# blinky_tag_smt_ver_1.net
KiCad netlist of a schematic drawn in EAGLE
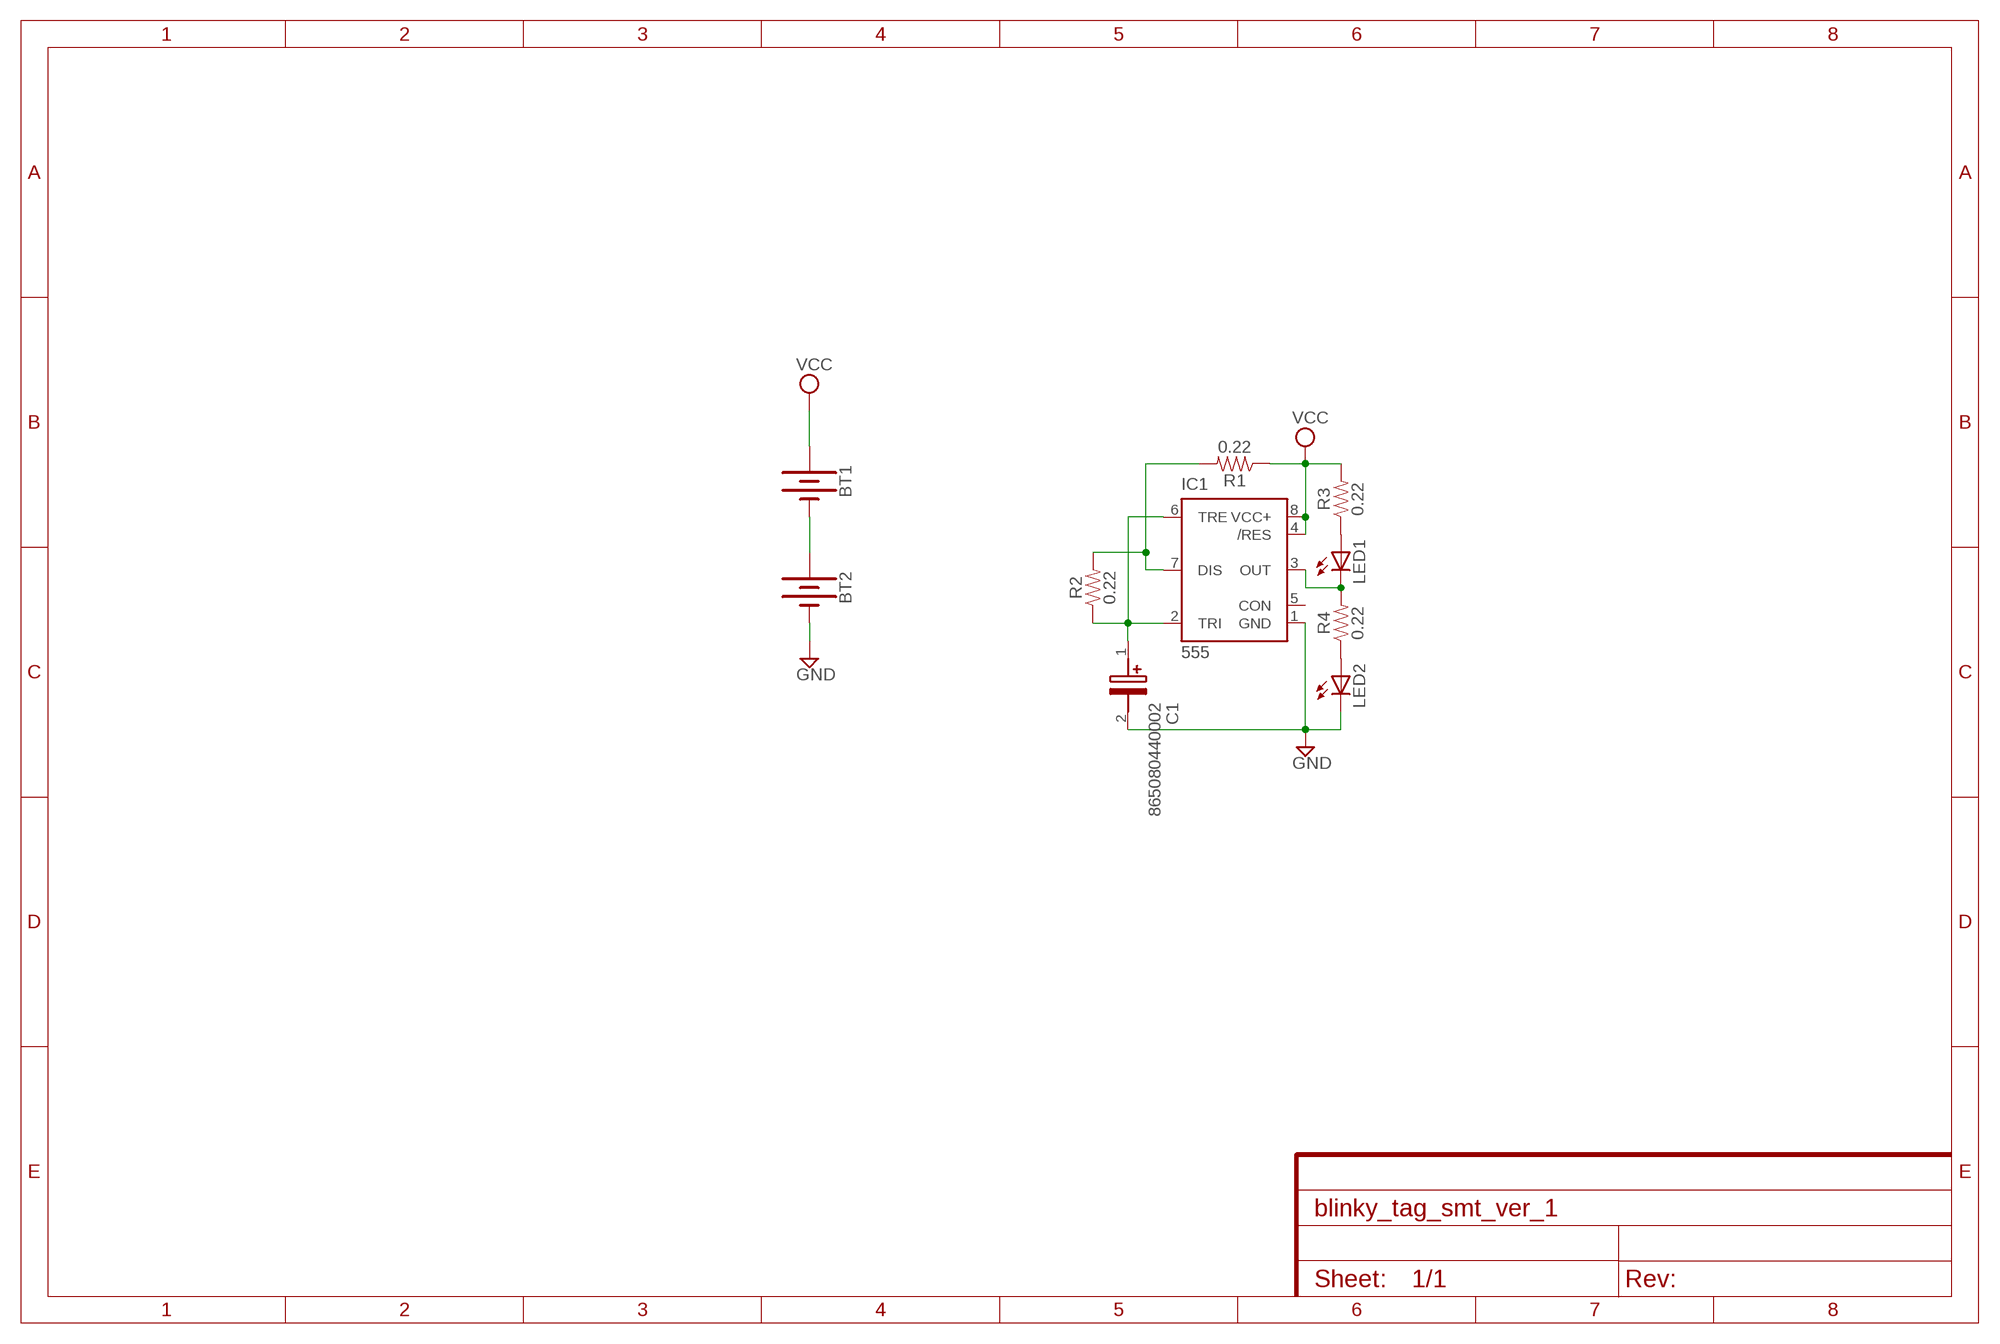
[diagram p0: schematic, sheet 1]

(export (version "E")
  (design (tool "Eeschema 10.0.6"))
  (components
    (comp (ref "BT1")
      (value "BATTERY-12MM_SMD")
      (footprint "eagle-import:BATTCON_12MM")
      (libsource (lib "eagle-import") (part "BATTERY-12MM_SMD"))
    )
    (comp (ref "BT2")
      (value "BATTERY-12MM_SMD")
      (footprint "eagle-import:BATTCON_12MM")
      (libsource (lib "eagle-import") (part "BATTERY-12MM_SMD"))
    )
    (comp (ref "C1")
      (value "865080440002")
      (footprint "eagle-import:CAPAE400X550N")
      (fields
        (field (name "MOUSER_PART_NUMBER") "710-865080440002")
        (field (name "RS_PART_NUMBER") "8391799P")
      )
      (libsource (lib "eagle-import") (part "865080440002"))
    )
    (comp (ref "IC1")
      (value "555")
      (footprint "eagle-import:SO08")
      (libsource (lib "eagle-import") (part "555D"))
    )
    (comp (ref "LED1")
      (value "LED5MM")
      (footprint "eagle-import:LED5MM")
      (libsource (lib "eagle-import") (part "LED5MM"))
    )
    (comp (ref "LED2")
      (value "LED5MM")
      (footprint "eagle-import:LED5MM")
      (libsource (lib "eagle-import") (part "LED5MM"))
    )
    (comp (ref "R1")
      (value "0.22")
      (footprint "eagle-import:0805")
      (libsource (lib "eagle-import") (part "0.22OHM-0805-1/4W-1%"))
    )
    (comp (ref "R2")
      (value "0.22")
      (footprint "eagle-import:0805")
      (libsource (lib "eagle-import") (part "0.22OHM-0805-1/4W-1%"))
    )
    (comp (ref "R3")
      (value "0.22")
      (footprint "eagle-import:0805")
      (libsource (lib "eagle-import") (part "0.22OHM-0805-1/4W-1%"))
    )
    (comp (ref "R4")
      (value "0.22")
      (footprint "eagle-import:0805")
      (libsource (lib "eagle-import") (part "0.22OHM-0805-1/4W-1%"))
    )
  )
  (nets
    (net (code "1") (name "GND") (class "Default")
      (node (ref "BT2") (pin "GND") (pinfunction "-_GND") (pintype "power_in"))
      (node (ref "C1") (pin "2") (pinfunction "-_2") (pintype "bidirectional"))
      (node (ref "IC1") (pin "1") (pinfunction "GND_1") (pintype "power_in"))
      (node (ref "LED2") (pin "K") (pinfunction "C_K") (pintype "passive"))
    )
    (net (code "2") (name "Net-(BT1--)") (class "Default")
      (node (ref "BT1") (pin "GND") (pinfunction "-_GND") (pintype "power_in"))
      (node (ref "BT2") (pin "PWR@1") (pinfunction "+_PWR@1") (pintype "power_in"))
    )
    (net (code "3") (name "Net-(C1-+)") (class "Default")
      (node (ref "C1") (pin "1") (pinfunction "+_1") (pintype "bidirectional"))
      (node (ref "IC1") (pin "2") (pinfunction "TRI_2") (pintype "input"))
      (node (ref "IC1") (pin "6") (pinfunction "TRE_6") (pintype "input"))
      (node (ref "R2") (pin "1") (pinfunction "1_1") (pintype "passive"))
    )
    (net (code "4") (name "Net-(IC1-DIS)") (class "Default")
      (node (ref "IC1") (pin "7") (pinfunction "DIS_7") (pintype "input"))
      (node (ref "R1") (pin "2") (pinfunction "2_2") (pintype "passive"))
      (node (ref "R2") (pin "2") (pinfunction "2_2") (pintype "passive"))
    )
    (net (code "5") (name "Net-(IC1-OUT)") (class "Default")
      (node (ref "IC1") (pin "3") (pinfunction "OUT_3") (pintype "output"))
      (node (ref "LED1") (pin "K") (pinfunction "C_K") (pintype "passive"))
      (node (ref "R4") (pin "2") (pinfunction "2_2") (pintype "passive"))
    )
    (net (code "6") (name "Net-(LED1-PadA)") (class "Default")
      (node (ref "LED1") (pin "A") (pinfunction "A_A") (pintype "passive"))
      (node (ref "R3") (pin "1") (pinfunction "1_1") (pintype "passive"))
    )
    (net (code "7") (name "Net-(LED2-PadA)") (class "Default")
      (node (ref "LED2") (pin "A") (pinfunction "A_A") (pintype "passive"))
      (node (ref "R4") (pin "1") (pinfunction "1_1") (pintype "passive"))
    )
    (net (code "8") (name "VCC") (class "Default")
      (node (ref "BT1") (pin "PWR@1") (pinfunction "+_PWR@1") (pintype "power_in"))
      (node (ref "IC1") (pin "4") (pinfunction "/RES_4") (pintype "input"))
      (node (ref "IC1") (pin "8") (pinfunction "VCC+_8") (pintype "power_in"))
      (node (ref "R1") (pin "1") (pinfunction "1_1") (pintype "passive"))
      (node (ref "R3") (pin "2") (pinfunction "2_2") (pintype "passive"))
    )
    (net (code "9") (name "unconnected-(IC1-CON-Pad5)") (class "Default")
      (node (ref "IC1") (pin "5") (pinfunction "CON_5") (pintype "input"))
    )
  )
)
